# schematic.net
KiCad netlist of a schematic drawn in EAGLE
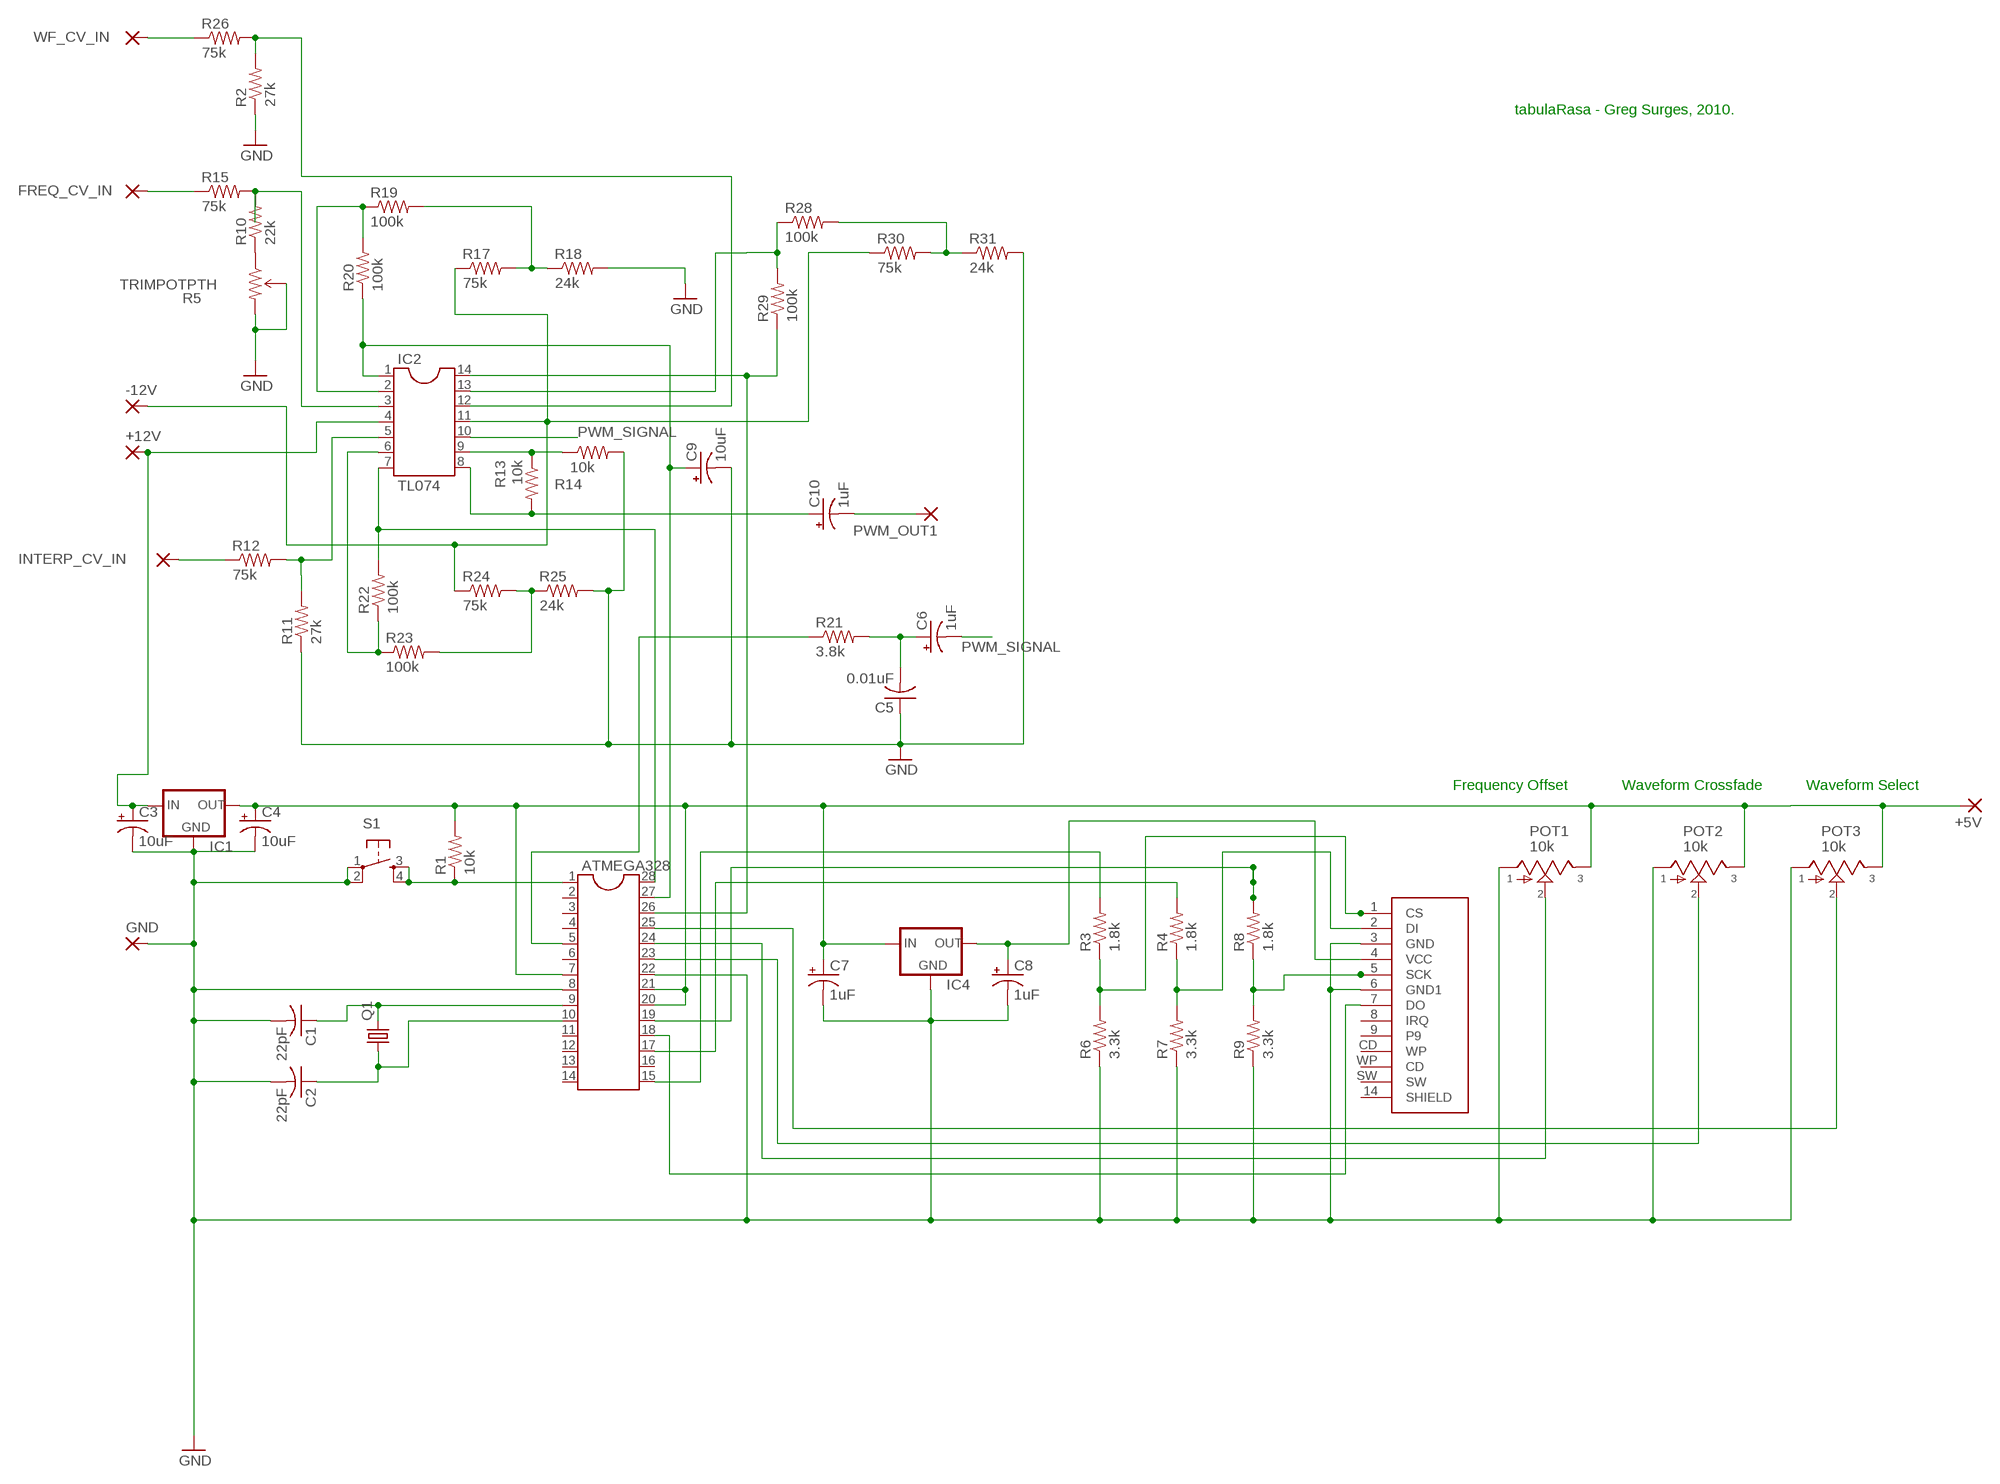
[diagram p0: schematic, sheet 1]

(export (version "E")
  (design (tool "Eeschema 10.0.6"))
  (components
    (comp (ref "+5V")
      (value "3,81/1,4")
      (footprint "eagle-import:3,81_1,4")
      (libsource (lib "eagle-import") (part "3,81/1,4"))
    )
    (comp (ref "+12V")
      (value "3,81/1,4")
      (footprint "eagle-import:3,81_1,4")
      (libsource (lib "eagle-import") (part "3,81/1,4"))
    )
    (comp (ref "-12V")
      (value "3,81/1,4")
      (footprint "eagle-import:3,81_1,4")
      (libsource (lib "eagle-import") (part "3,81/1,4"))
    )
    (comp (ref "ATMEGA328")
      (value "DIL28-3")
      (footprint "eagle-import:DIL28-3")
      (libsource (lib "eagle-import") (part "DIL28-3"))
    )
    (comp (ref "C1")
      (value "22pF")
      (footprint "eagle-import:C050-025X075")
      (libsource (lib "eagle-import") (part "C-US050-025X075"))
    )
    (comp (ref "C2")
      (value "22pF")
      (footprint "eagle-import:C050-025X075")
      (libsource (lib "eagle-import") (part "C-US050-025X075"))
    )
    (comp (ref "C3")
      (value "10uF")
      (footprint "eagle-import:E2,5-6")
      (libsource (lib "eagle-import") (part "CPOL-USE2.5-6"))
    )
    (comp (ref "C4")
      (value "10uF")
      (footprint "eagle-import:E2,5-6")
      (libsource (lib "eagle-import") (part "CPOL-USE2.5-6"))
    )
    (comp (ref "C5")
      (value "0.01uF")
      (footprint "eagle-import:C050-025X075")
      (libsource (lib "eagle-import") (part "C-US050-025X075"))
    )
    (comp (ref "C6")
      (value "1uF")
      (footprint "eagle-import:E2,5-6")
      (libsource (lib "eagle-import") (part "CPOL-USE2.5-6"))
    )
    (comp (ref "C7")
      (value "1uF")
      (footprint "eagle-import:E2,5-6")
      (libsource (lib "eagle-import") (part "CPOL-USE2.5-6"))
    )
    (comp (ref "C8")
      (value "1uF")
      (footprint "eagle-import:E2,5-6")
      (libsource (lib "eagle-import") (part "CPOL-USE2.5-6"))
    )
    (comp (ref "C9")
      (value "10uF")
      (footprint "eagle-import:E2,5-6")
      (libsource (lib "eagle-import") (part "CPOL-USE2.5-6"))
    )
    (comp (ref "C10")
      (value "1uF")
      (footprint "eagle-import:E2,5-6")
      (libsource (lib "eagle-import") (part "CPOL-USE2.5-6"))
    )
    (comp (ref "FREQ_CV_IN")
      (value "3,81/1,4")
      (footprint "eagle-import:3,81_1,4")
      (libsource (lib "eagle-import") (part "3,81/1,4"))
    )
    (comp (ref "GND")
      (value "3,81/1,4")
      (footprint "eagle-import:3,81_1,4")
      (libsource (lib "eagle-import") (part "3,81/1,4"))
    )
    (comp (ref "IC1")
      (value "V_REG_78XXSIDE")
      (footprint "eagle-import:78XXL")
      (libsource (lib "eagle-import") (part "V_REG_78XXSIDE"))
    )
    (comp (ref "IC2")
      (value "TL074")
      (footprint "eagle-import:DIL14")
      (libsource (lib "eagle-import") (part "DIL14"))
    )
    (comp (ref "IC4")
      (value "MCP1700INLINE")
      (footprint "eagle-import:TO92-INLINE")
      (libsource (lib "eagle-import") (part "MCP1700INLINE"))
    )
    (comp (ref "INTERP_CV_IN")
      (value "3,81/1,4")
      (footprint "eagle-import:3,81_1,4")
      (libsource (lib "eagle-import") (part "3,81/1,4"))
    )
    (comp (ref "POT1")
      (value "10k")
      (footprint "eagle-import:16MM-PCB-MOUNT")
      (libsource (lib "eagle-import") (part "POTPCB"))
    )
    (comp (ref "POT2")
      (value "10k")
      (footprint "eagle-import:16MM-PCB-MOUNT")
      (libsource (lib "eagle-import") (part "POTPCB"))
    )
    (comp (ref "POT3")
      (value "10k")
      (footprint "eagle-import:16MM-PCB-MOUNT")
      (libsource (lib "eagle-import") (part "POTPCB"))
    )
    (comp (ref "PWM_OUT1")
      (value "3,81/1,4")
      (footprint "eagle-import:3,81_1,4")
      (libsource (lib "eagle-import") (part "3,81/1,4"))
    )
    (comp (ref "Q1")
      (value "CRYSTALHC49US")
      (footprint "eagle-import:HC49US")
      (libsource (lib "eagle-import") (part "CRYSTALHC49US"))
    )
    (comp (ref "R1")
      (value "10k")
      (footprint "eagle-import:0411_12")
      (libsource (lib "eagle-import") (part "R-US_0411/12"))
    )
    (comp (ref "R2")
      (value "27k")
      (footprint "eagle-import:0411_12")
      (libsource (lib "eagle-import") (part "R-US_0411/12"))
    )
    (comp (ref "R3")
      (value "1.8k")
      (footprint "eagle-import:0411_12")
      (libsource (lib "eagle-import") (part "R-US_0411/12"))
    )
    (comp (ref "R4")
      (value "1.8k")
      (footprint "eagle-import:0411_12")
      (libsource (lib "eagle-import") (part "R-US_0411/12"))
    )
    (comp (ref "R5")
      (value "TRIMPOTPTH")
      (footprint "eagle-import:TRIM_POT_PTH")
      (libsource (lib "eagle-import") (part "TRIMPOTPTH"))
    )
    (comp (ref "R6")
      (value "3.3k")
      (footprint "eagle-import:0411_12")
      (libsource (lib "eagle-import") (part "R-US_0411/12"))
    )
    (comp (ref "R7")
      (value "3.3k")
      (footprint "eagle-import:0411_12")
      (libsource (lib "eagle-import") (part "R-US_0411/12"))
    )
    (comp (ref "R8")
      (value "1.8k")
      (footprint "eagle-import:0411_12")
      (libsource (lib "eagle-import") (part "R-US_0411/12"))
    )
    (comp (ref "R9")
      (value "3.3k")
      (footprint "eagle-import:0411_12")
      (libsource (lib "eagle-import") (part "R-US_0411/12"))
    )
    (comp (ref "R10")
      (value "22k")
      (footprint "eagle-import:0411_12")
      (libsource (lib "eagle-import") (part "R-US_0411/12"))
    )
    (comp (ref "R11")
      (value "27k")
      (footprint "eagle-import:0411_12")
      (libsource (lib "eagle-import") (part "R-US_0411/12"))
    )
    (comp (ref "R12")
      (value "75k")
      (footprint "eagle-import:0411_12")
      (libsource (lib "eagle-import") (part "R-US_0411/12"))
    )
    (comp (ref "R13")
      (value "10k")
      (footprint "eagle-import:0411_12")
      (libsource (lib "eagle-import") (part "R-US_0411/12"))
    )
    (comp (ref "R14")
      (value "10k")
      (footprint "eagle-import:0411_12")
      (libsource (lib "eagle-import") (part "R-US_0411/12"))
    )
    (comp (ref "R15")
      (value "75k")
      (footprint "eagle-import:0411_12")
      (libsource (lib "eagle-import") (part "R-US_0411/12"))
    )
    (comp (ref "R17")
      (value "75k")
      (footprint "eagle-import:0411_12")
      (libsource (lib "eagle-import") (part "R-US_0411/12"))
    )
    (comp (ref "R18")
      (value "24k")
      (footprint "eagle-import:0411_12")
      (libsource (lib "eagle-import") (part "R-US_0411/12"))
    )
    (comp (ref "R19")
      (value "100k")
      (footprint "eagle-import:0411_12")
      (libsource (lib "eagle-import") (part "R-US_0411/12"))
    )
    (comp (ref "R20")
      (value "100k")
      (footprint "eagle-import:0411_12")
      (libsource (lib "eagle-import") (part "R-US_0411/12"))
    )
    (comp (ref "R21")
      (value "3.8k")
      (footprint "eagle-import:0411_12")
      (libsource (lib "eagle-import") (part "R-US_0411/12"))
    )
    (comp (ref "R22")
      (value "100k")
      (footprint "eagle-import:0411_12")
      (libsource (lib "eagle-import") (part "R-US_0411/12"))
    )
    (comp (ref "R23")
      (value "100k")
      (footprint "eagle-import:0411_12")
      (libsource (lib "eagle-import") (part "R-US_0411/12"))
    )
    (comp (ref "R24")
      (value "75k")
      (footprint "eagle-import:0411_12")
      (libsource (lib "eagle-import") (part "R-US_0411/12"))
    )
    (comp (ref "R25")
      (value "24k")
      (footprint "eagle-import:0411_12")
      (libsource (lib "eagle-import") (part "R-US_0411/12"))
    )
    (comp (ref "R26")
      (value "75k")
      (footprint "eagle-import:0411_12")
      (libsource (lib "eagle-import") (part "R-US_0411/12"))
    )
    (comp (ref "R28")
      (value "100k")
      (footprint "eagle-import:0411_12")
      (libsource (lib "eagle-import") (part "R-US_0411/12"))
    )
    (comp (ref "R29")
      (value "100k")
      (footprint "eagle-import:0411_12")
      (libsource (lib "eagle-import") (part "R-US_0411/12"))
    )
    (comp (ref "R30")
      (value "75k")
      (footprint "eagle-import:0411_12")
      (libsource (lib "eagle-import") (part "R-US_0411/12"))
    )
    (comp (ref "R31")
      (value "24k")
      (footprint "eagle-import:0411_12")
      (libsource (lib "eagle-import") (part "R-US_0411/12"))
    )
    (comp (ref "S1")
      (value "TAC_SWITCHPTH")
      (footprint "eagle-import:TACTILE-PTH")
      (libsource (lib "eagle-import") (part "TAC_SWITCHPTH"))
    )
    (comp (ref "U$1")
      (value "SD_CARD_SOCKETSD")
      (footprint "eagle-import:SD-MMC_SOCKET-PP")
      (libsource (lib "eagle-import") (part "SD_CARD_SOCKETSD"))
    )
    (comp (ref "WF_CV_IN")
      (value "3,81/1,4")
      (footprint "eagle-import:3,81_1,4")
      (libsource (lib "eagle-import") (part "3,81/1,4"))
    )
  )
  (nets
    (net (code "1") (name "/PWM_SIGNAL") (class "Default")
      (node (ref "C6") (pin "-") (pinfunction "-_-") (pintype "passive"))
      (node (ref "IC2") (pin "10") (pinfunction "10_10") (pintype "passive"))
    )
    (net (code "2") (name "GND") (class "Default")
      (node (ref "ATMEGA328") (pin "22") (pinfunction "22_22") (pintype "passive"))
      (node (ref "ATMEGA328") (pin "8") (pinfunction "8_8") (pintype "passive"))
      (node (ref "C1") (pin "2") (pinfunction "2_2") (pintype "passive"))
      (node (ref "C2") (pin "2") (pinfunction "2_2") (pintype "passive"))
      (node (ref "C3") (pin "-") (pinfunction "-_-") (pintype "passive"))
      (node (ref "C4") (pin "-") (pinfunction "-_-") (pintype "passive"))
      (node (ref "C5") (pin "1") (pinfunction "1_1") (pintype "passive"))
      (node (ref "C7") (pin "-") (pinfunction "-_-") (pintype "passive"))
      (node (ref "C8") (pin "-") (pinfunction "-_-") (pintype "passive"))
      (node (ref "C9") (pin "-") (pinfunction "-_-") (pintype "passive"))
      (node (ref "GND") (pin "1") (pinfunction "P_1") (pintype "passive"))
      (node (ref "IC1") (pin "GND") (pinfunction "GND_GND") (pintype "input"))
      (node (ref "IC4") (pin "1") (pinfunction "GND_1") (pintype "input"))
      (node (ref "POT1") (pin "1") (pinfunction "1_1") (pintype "passive"))
      (node (ref "POT2") (pin "1") (pinfunction "1_1") (pintype "passive"))
      (node (ref "POT3") (pin "1") (pinfunction "1_1") (pintype "passive"))
      (node (ref "R11") (pin "1") (pinfunction "1_1") (pintype "passive"))
      (node (ref "R14") (pin "2") (pinfunction "2_2") (pintype "passive"))
      (node (ref "R18") (pin "2") (pinfunction "2_2") (pintype "passive"))
      (node (ref "R2") (pin "1") (pinfunction "1_1") (pintype "passive"))
      (node (ref "R25") (pin "2") (pinfunction "2_2") (pintype "passive"))
      (node (ref "R31") (pin "2") (pinfunction "2_2") (pintype "passive"))
      (node (ref "R5") (pin "2") (pinfunction "WIPER_2") (pintype "passive"))
      (node (ref "R5") (pin "3") (pinfunction "CW_3") (pintype "passive"))
      (node (ref "R6") (pin "1") (pinfunction "1_1") (pintype "passive"))
      (node (ref "R7") (pin "1") (pinfunction "1_1") (pintype "passive"))
      (node (ref "R9") (pin "1") (pinfunction "1_1") (pintype "passive"))
      (node (ref "S1") (pin "1") (pinfunction "1_1") (pintype "passive"))
      (node (ref "S1") (pin "2") (pinfunction "2_2") (pintype "passive"))
      (node (ref "U$1") (pin "3") (pinfunction "GND_3") (pintype "bidirectional"))
      (node (ref "U$1") (pin "6") (pinfunction "GND1_6") (pintype "bidirectional"))
    )
    (net (code "3") (name "Net-(+5V-P)") (class "Default")
      (node (ref "+5V") (pin "1") (pinfunction "P_1") (pintype "passive"))
      (node (ref "ATMEGA328") (pin "20") (pinfunction "20_20") (pintype "passive"))
      (node (ref "ATMEGA328") (pin "21") (pinfunction "21_21") (pintype "passive"))
      (node (ref "ATMEGA328") (pin "7") (pinfunction "7_7") (pintype "passive"))
      (node (ref "C4") (pin "+") (pinfunction "+_+") (pintype "passive"))
      (node (ref "C7") (pin "+") (pinfunction "+_+") (pintype "passive"))
      (node (ref "IC1") (pin "OUT") (pinfunction "OUT_OUT") (pintype "output"))
      (node (ref "IC4") (pin "2") (pinfunction "IN_2") (pintype "input"))
      (node (ref "POT1") (pin "3") (pinfunction "3_3") (pintype "passive"))
      (node (ref "POT2") (pin "3") (pinfunction "3_3") (pintype "passive"))
      (node (ref "POT3") (pin "3") (pinfunction "3_3") (pintype "passive"))
      (node (ref "R1") (pin "2") (pinfunction "2_2") (pintype "passive"))
    )
    (net (code "4") (name "Net-(+12V-P)") (class "Default")
      (node (ref "+12V") (pin "1") (pinfunction "P_1") (pintype "passive"))
      (node (ref "C3") (pin "+") (pinfunction "+_+") (pintype "passive"))
      (node (ref "IC1") (pin "IN") (pinfunction "IN_IN") (pintype "input"))
      (node (ref "IC2") (pin "4") (pinfunction "4_4") (pintype "passive"))
    )
    (net (code "5") (name "Net-(-12V-P)") (class "Default")
      (node (ref "-12V") (pin "1") (pinfunction "P_1") (pintype "passive"))
      (node (ref "IC2") (pin "11") (pinfunction "11_11") (pintype "passive"))
      (node (ref "R17") (pin "1") (pinfunction "1_1") (pintype "passive"))
      (node (ref "R24") (pin "1") (pinfunction "1_1") (pintype "passive"))
      (node (ref "R30") (pin "1") (pinfunction "1_1") (pintype "passive"))
    )
    (net (code "6") (name "Net-(ATMEGA328-Pad1)") (class "Default")
      (node (ref "ATMEGA328") (pin "1") (pinfunction "1_1") (pintype "passive"))
      (node (ref "R1") (pin "1") (pinfunction "1_1") (pintype "passive"))
      (node (ref "S1") (pin "3") (pinfunction "3_3") (pintype "passive"))
      (node (ref "S1") (pin "4") (pinfunction "4_4") (pintype "passive"))
    )
    (net (code "7") (name "Net-(ATMEGA328-Pad5)") (class "Default")
      (node (ref "ATMEGA328") (pin "5") (pinfunction "5_5") (pintype "passive"))
      (node (ref "R21") (pin "1") (pinfunction "1_1") (pintype "passive"))
    )
    (net (code "8") (name "Net-(ATMEGA328-Pad9)") (class "Default")
      (node (ref "ATMEGA328") (pin "9") (pinfunction "9_9") (pintype "passive"))
      (node (ref "C1") (pin "1") (pinfunction "1_1") (pintype "passive"))
      (node (ref "Q1") (pin "2") (pinfunction "2_2") (pintype "passive"))
    )
    (net (code "9") (name "Net-(ATMEGA328-Pad10)") (class "Default")
      (node (ref "ATMEGA328") (pin "10") (pinfunction "10_10") (pintype "passive"))
      (node (ref "C2") (pin "1") (pinfunction "1_1") (pintype "passive"))
      (node (ref "Q1") (pin "1") (pinfunction "1_1") (pintype "passive"))
    )
    (net (code "10") (name "Net-(ATMEGA328-Pad15)") (class "Default")
      (node (ref "ATMEGA328") (pin "15") (pinfunction "15_15") (pintype "passive"))
      (node (ref "R3") (pin "2") (pinfunction "2_2") (pintype "passive"))
    )
    (net (code "11") (name "Net-(ATMEGA328-Pad17)") (class "Default")
      (node (ref "ATMEGA328") (pin "17") (pinfunction "17_17") (pintype "passive"))
      (node (ref "R4") (pin "2") (pinfunction "2_2") (pintype "passive"))
    )
    (net (code "12") (name "Net-(ATMEGA328-Pad19)") (class "Default")
      (node (ref "ATMEGA328") (pin "19") (pinfunction "19_19") (pintype "passive"))
      (node (ref "R8") (pin "2") (pinfunction "2_2") (pintype "passive"))
    )
    (net (code "13") (name "Net-(ATMEGA328-Pad23)") (class "Default")
      (node (ref "ATMEGA328") (pin "23") (pinfunction "23_23") (pintype "passive"))
      (node (ref "POT2") (pin "2") (pinfunction "2_2") (pintype "passive"))
    )
    (net (code "14") (name "Net-(ATMEGA328-Pad24)") (class "Default")
      (node (ref "ATMEGA328") (pin "24") (pinfunction "24_24") (pintype "passive"))
      (node (ref "POT1") (pin "2") (pinfunction "2_2") (pintype "passive"))
    )
    (net (code "15") (name "Net-(ATMEGA328-Pad25)") (class "Default")
      (node (ref "ATMEGA328") (pin "25") (pinfunction "25_25") (pintype "passive"))
      (node (ref "POT3") (pin "2") (pinfunction "2_2") (pintype "passive"))
    )
    (net (code "16") (name "Net-(ATMEGA328-Pad26)") (class "Default")
      (node (ref "ATMEGA328") (pin "26") (pinfunction "26_26") (pintype "passive"))
      (node (ref "IC2") (pin "14") (pinfunction "14_14") (pintype "passive"))
      (node (ref "R29") (pin "1") (pinfunction "1_1") (pintype "passive"))
    )
    (net (code "17") (name "Net-(ATMEGA328-Pad27)") (class "Default")
      (node (ref "ATMEGA328") (pin "27") (pinfunction "27_27") (pintype "passive"))
      (node (ref "C9") (pin "+") (pinfunction "+_+") (pintype "passive"))
      (node (ref "IC2") (pin "1") (pinfunction "1_1") (pintype "passive"))
      (node (ref "R20") (pin "1") (pinfunction "1_1") (pintype "passive"))
    )
    (net (code "18") (name "Net-(ATMEGA328-Pad28)") (class "Default")
      (node (ref "ATMEGA328") (pin "28") (pinfunction "28_28") (pintype "passive"))
      (node (ref "IC2") (pin "7") (pinfunction "7_7") (pintype "passive"))
      (node (ref "R22") (pin "2") (pinfunction "2_2") (pintype "passive"))
    )
    (net (code "19") (name "Net-(C5-Pad2)") (class "Default")
      (node (ref "C5") (pin "2") (pinfunction "2_2") (pintype "passive"))
      (node (ref "C6") (pin "+") (pinfunction "+_+") (pintype "passive"))
      (node (ref "R21") (pin "2") (pinfunction "2_2") (pintype "passive"))
    )
    (net (code "20") (name "Net-(C10-Pad+)") (class "Default")
      (node (ref "C10") (pin "+") (pinfunction "+_+") (pintype "passive"))
      (node (ref "IC2") (pin "8") (pinfunction "8_8") (pintype "passive"))
      (node (ref "R13") (pin "2") (pinfunction "2_2") (pintype "passive"))
    )
    (net (code "21") (name "Net-(FREQ_CV_IN-P)") (class "Default")
      (node (ref "FREQ_CV_IN") (pin "1") (pinfunction "P_1") (pintype "passive"))
      (node (ref "R15") (pin "1") (pinfunction "1_1") (pintype "passive"))
    )
    (net (code "22") (name "Net-(IC2-Pad2)") (class "Default")
      (node (ref "IC2") (pin "2") (pinfunction "2_2") (pintype "passive"))
      (node (ref "R19") (pin "1") (pinfunction "1_1") (pintype "passive"))
      (node (ref "R20") (pin "2") (pinfunction "2_2") (pintype "passive"))
    )
    (net (code "23") (name "Net-(IC2-Pad3)") (class "Default")
      (node (ref "IC2") (pin "3") (pinfunction "3_3") (pintype "passive"))
      (node (ref "R10") (pin "2") (pinfunction "2_2") (pintype "passive"))
      (node (ref "R15") (pin "2") (pinfunction "2_2") (pintype "passive"))
    )
    (net (code "24") (name "Net-(IC2-Pad5)") (class "Default")
      (node (ref "IC2") (pin "5") (pinfunction "5_5") (pintype "passive"))
      (node (ref "R11") (pin "2") (pinfunction "2_2") (pintype "passive"))
      (node (ref "R12") (pin "2") (pinfunction "2_2") (pintype "passive"))
    )
    (net (code "25") (name "Net-(IC2-Pad6)") (class "Default")
      (node (ref "IC2") (pin "6") (pinfunction "6_6") (pintype "passive"))
      (node (ref "R22") (pin "1") (pinfunction "1_1") (pintype "passive"))
      (node (ref "R23") (pin "1") (pinfunction "1_1") (pintype "passive"))
    )
    (net (code "26") (name "Net-(IC2-Pad9)") (class "Default")
      (node (ref "IC2") (pin "9") (pinfunction "9_9") (pintype "passive"))
      (node (ref "R13") (pin "1") (pinfunction "1_1") (pintype "passive"))
      (node (ref "R14") (pin "1") (pinfunction "1_1") (pintype "passive"))
    )
    (net (code "27") (name "Net-(IC2-Pad12)") (class "Default")
      (node (ref "IC2") (pin "12") (pinfunction "12_12") (pintype "passive"))
      (node (ref "R2") (pin "2") (pinfunction "2_2") (pintype "passive"))
      (node (ref "R26") (pin "2") (pinfunction "2_2") (pintype "passive"))
    )
    (net (code "28") (name "Net-(IC2-Pad13)") (class "Default")
      (node (ref "IC2") (pin "13") (pinfunction "13_13") (pintype "passive"))
      (node (ref "R28") (pin "1") (pinfunction "1_1") (pintype "passive"))
      (node (ref "R29") (pin "2") (pinfunction "2_2") (pintype "passive"))
    )
    (net (code "29") (name "Net-(IC4-OUT)") (class "Default")
      (node (ref "C8") (pin "+") (pinfunction "+_+") (pintype "passive"))
      (node (ref "IC4") (pin "3") (pinfunction "OUT_3") (pintype "passive"))
      (node (ref "U$1") (pin "4") (pinfunction "VCC_4") (pintype "bidirectional"))
    )
    (net (code "30") (name "Net-(INTERP_CV_IN-P)") (class "Default")
      (node (ref "INTERP_CV_IN") (pin "1") (pinfunction "P_1") (pintype "passive"))
      (node (ref "R12") (pin "1") (pinfunction "1_1") (pintype "passive"))
    )
    (net (code "31") (name "Net-(PWM_OUT1-P)") (class "Default")
      (node (ref "C10") (pin "-") (pinfunction "-_-") (pintype "passive"))
      (node (ref "PWM_OUT1") (pin "1") (pinfunction "P_1") (pintype "passive"))
    )
    (net (code "32") (name "Net-(R5-CCW)") (class "Default")
      (node (ref "R10") (pin "1") (pinfunction "1_1") (pintype "passive"))
      (node (ref "R5") (pin "1") (pinfunction "CCW_1") (pintype "passive"))
    )
    (net (code "33") (name "Net-(R17-Pad2)") (class "Default")
      (node (ref "R17") (pin "2") (pinfunction "2_2") (pintype "passive"))
      (node (ref "R18") (pin "1") (pinfunction "1_1") (pintype "passive"))
      (node (ref "R19") (pin "2") (pinfunction "2_2") (pintype "passive"))
    )
    (net (code "34") (name "Net-(R23-Pad2)") (class "Default")
      (node (ref "R23") (pin "2") (pinfunction "2_2") (pintype "passive"))
      (node (ref "R24") (pin "2") (pinfunction "2_2") (pintype "passive"))
      (node (ref "R25") (pin "1") (pinfunction "1_1") (pintype "passive"))
    )
    (net (code "35") (name "Net-(R28-Pad2)") (class "Default")
      (node (ref "R28") (pin "2") (pinfunction "2_2") (pintype "passive"))
      (node (ref "R30") (pin "2") (pinfunction "2_2") (pintype "passive"))
      (node (ref "R31") (pin "1") (pinfunction "1_1") (pintype "passive"))
    )
    (net (code "36") (name "Net-(U$1-CS)") (class "Default")
      (node (ref "R3") (pin "1") (pinfunction "1_1") (pintype "passive"))
      (node (ref "R6") (pin "2") (pinfunction "2_2") (pintype "passive"))
      (node (ref "U$1") (pin "1") (pinfunction "CS_1") (pintype "bidirectional"))
    )
    (net (code "37") (name "Net-(U$1-DI)") (class "Default")
      (node (ref "R4") (pin "1") (pinfunction "1_1") (pintype "passive"))
      (node (ref "R7") (pin "2") (pinfunction "2_2") (pintype "passive"))
      (node (ref "U$1") (pin "2") (pinfunction "DI_2") (pintype "bidirectional"))
    )
    (net (code "38") (name "Net-(U$1-DO)") (class "Default")
      (node (ref "ATMEGA328") (pin "18") (pinfunction "18_18") (pintype "passive"))
      (node (ref "U$1") (pin "7") (pinfunction "DO_7") (pintype "bidirectional"))
    )
    (net (code "39") (name "Net-(U$1-SCK)") (class "Default")
      (node (ref "R8") (pin "1") (pinfunction "1_1") (pintype "passive"))
      (node (ref "R9") (pin "2") (pinfunction "2_2") (pintype "passive"))
      (node (ref "U$1") (pin "5") (pinfunction "SCK_5") (pintype "bidirectional"))
    )
    (net (code "40") (name "Net-(WF_CV_IN-P)") (class "Default")
      (node (ref "R26") (pin "1") (pinfunction "1_1") (pintype "passive"))
      (node (ref "WF_CV_IN") (pin "1") (pinfunction "P_1") (pintype "passive"))
    )
    (net (code "41") (name "unconnected-(ATMEGA328-Pad2)") (class "Default")
      (node (ref "ATMEGA328") (pin "2") (pinfunction "2_2") (pintype "passive"))
    )
    (net (code "42") (name "unconnected-(ATMEGA328-Pad3)") (class "Default")
      (node (ref "ATMEGA328") (pin "3") (pinfunction "3_3") (pintype "passive"))
    )
    (net (code "43") (name "unconnected-(ATMEGA328-Pad4)") (class "Default")
      (node (ref "ATMEGA328") (pin "4") (pinfunction "4_4") (pintype "passive"))
    )
    (net (code "44") (name "unconnected-(ATMEGA328-Pad6)") (class "Default")
      (node (ref "ATMEGA328") (pin "6") (pinfunction "6_6") (pintype "passive"))
    )
    (net (code "45") (name "unconnected-(ATMEGA328-Pad11)") (class "Default")
      (node (ref "ATMEGA328") (pin "11") (pinfunction "11_11") (pintype "passive"))
    )
    (net (code "46") (name "unconnected-(ATMEGA328-Pad12)") (class "Default")
      (node (ref "ATMEGA328") (pin "12") (pinfunction "12_12") (pintype "passive"))
    )
    (net (code "47") (name "unconnected-(ATMEGA328-Pad13)") (class "Default")
      (node (ref "ATMEGA328") (pin "13") (pinfunction "13_13") (pintype "passive"))
    )
    (net (code "48") (name "unconnected-(ATMEGA328-Pad14)") (class "Default")
      (node (ref "ATMEGA328") (pin "14") (pinfunction "14_14") (pintype "passive"))
    )
    (net (code "49") (name "unconnected-(ATMEGA328-Pad16)") (class "Default")
      (node (ref "ATMEGA328") (pin "16") (pinfunction "16_16") (pintype "passive"))
    )
    (net (code "50") (name "unconnected-(U$1-CD-PadWP)") (class "Default")
      (node (ref "U$1") (pin "WP") (pinfunction "CD_WP") (pintype "bidirectional"))
    )
    (net (code "51") (name "unconnected-(U$1-IRQ-Pad8)") (class "Default")
      (node (ref "U$1") (pin "8") (pinfunction "IRQ_8") (pintype "bidirectional"))
    )
    (net (code "52") (name "unconnected-(U$1-P9-Pad9)") (class "Default")
      (node (ref "U$1") (pin "9") (pinfunction "P9_9") (pintype "bidirectional"))
    )
    (net (code "53") (name "unconnected-(U$1-PadSW)") (class "Default")
      (node (ref "U$1") (pin "SW") (pinfunction "SW_SW") (pintype "bidirectional"))
    )
    (net (code "54") (name "unconnected-(U$1-SHIELD-Pad14)") (class "Default")
      (node (ref "U$1") (pin "14") (pinfunction "SHIELD_14") (pintype "bidirectional"))
    )
    (net (code "55") (name "unconnected-(U$1-WP-PadCD)") (class "Default")
      (node (ref "U$1") (pin "CD") (pinfunction "WP_CD") (pintype "bidirectional"))
    )
  )
)
